# power.net
KiCad netlist of a schematic drawn in Altium Designer
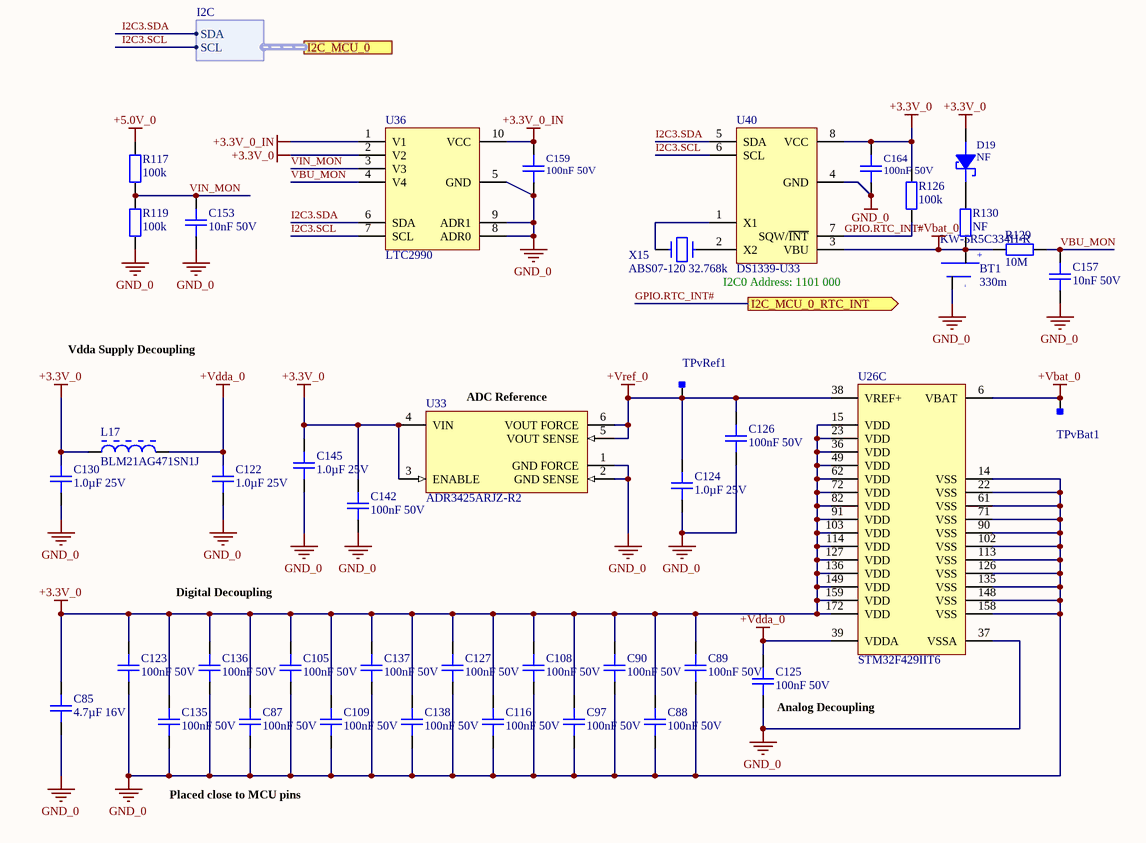
[diagram p0: power.SchDoc]

(export (version "E")
  (design (tool "Eeschema 10.0.6"))
  (components
    (comp (ref "BT1")
      (value "330m")
      (footprint "KW-5R5C")
      (description "Eaton 330mF, 5.5v, -20 to +80, Ultracapacitor, KW-5R5C334H-R")
      (fields (field (name "SUPPLIER PART NUMBER 1") "KW-5R5C334H-R"))
      (libsource (lib "master-010106") (part "BATTERY_1"))
    )
    (comp (ref "C85")
      (value "4.7µF 16V")
      (footprint "0805C")
      (description "Ceramic, 4.7µF, ±10%, 16V, X7R, –55 to 125°C, 0805 (2012),RoHS, Automotive")
      (fields (field (name "PART NUMBER") "GCJ21BR71C475KA01") (field (name "TOLERANCE") "±10%"))
      (libsource (lib "master-010106") (part "gen_C_ceramic_4u7_16V_X7R_0805"))
    )
    (comp (ref "C87")
      (value "100nF 50V")
      (footprint "0402C")
      (description "Ceramic, 100nF, ±10%, 50V, X7R, –55 to 125°C, 0402 (1005),RoHS, Automotive")
      (fields (field (name "PART NUMBER") "GCM155R71H104KE02") (field (name "TOLERANCE") "±10%"))
      (libsource (lib "master-010106") (part "gen_C_ceramic_100n_50V_X7R_0402"))
    )
    (comp (ref "C88")
      (value "100nF 50V")
      (footprint "0402C")
      (description "Ceramic, 100nF, ±10%, 50V, X7R, –55 to 125°C, 0402 (1005),RoHS, Automotive")
      (fields (field (name "PART NUMBER") "GCM155R71H104KE02") (field (name "TOLERANCE") "±10%"))
      (libsource (lib "master-010106") (part "gen_C_ceramic_100n_50V_X7R_0402"))
    )
    (comp (ref "C89")
      (value "100nF 50V")
      (footprint "0402C")
      (description "Ceramic, 100nF, ±10%, 50V, X7R, –55 to 125°C, 0402 (1005),RoHS, Automotive")
      (fields (field (name "PART NUMBER") "GCM155R71H104KE02") (field (name "TOLERANCE") "±10%"))
      (libsource (lib "master-010106") (part "gen_C_ceramic_100n_50V_X7R_0402"))
    )
    (comp (ref "C90")
      (value "100nF 50V")
      (footprint "0402C")
      (description "Ceramic, 100nF, ±10%, 50V, X7R, –55 to 125°C, 0402 (1005),RoHS, Automotive")
      (fields (field (name "PART NUMBER") "GCM155R71H104KE02") (field (name "TOLERANCE") "±10%"))
      (libsource (lib "master-010106") (part "gen_C_ceramic_100n_50V_X7R_0402"))
    )
    (comp (ref "C97")
      (value "100nF 50V")
      (footprint "0402C")
      (description "Ceramic, 100nF, ±10%, 50V, X7R, –55 to 125°C, 0402 (1005),RoHS, Automotive")
      (fields (field (name "PART NUMBER") "GCM155R71H104KE02") (field (name "TOLERANCE") "±10%"))
      (libsource (lib "master-010106") (part "gen_C_ceramic_100n_50V_X7R_0402"))
    )
    (comp (ref "C105")
      (value "100nF 50V")
      (footprint "0402C")
      (description "Ceramic, 100nF, ±10%, 50V, X7R, –55 to 125°C, 0402 (1005),RoHS, Automotive")
      (fields (field (name "PART NUMBER") "GCM155R71H104KE02") (field (name "TOLERANCE") "±10%"))
      (libsource (lib "master-010106") (part "gen_C_ceramic_100n_50V_X7R_0402"))
    )
    (comp (ref "C108")
      (value "100nF 50V")
      (footprint "0402C")
      (description "Ceramic, 100nF, ±10%, 50V, X7R, –55 to 125°C, 0402 (1005),RoHS, Automotive")
      (fields (field (name "PART NUMBER") "GCM155R71H104KE02") (field (name "TOLERANCE") "±10%"))
      (libsource (lib "master-010106") (part "gen_C_ceramic_100n_50V_X7R_0402"))
    )
    (comp (ref "C109")
      (value "100nF 50V")
      (footprint "0402C")
      (description "Ceramic, 100nF, ±10%, 50V, X7R, –55 to 125°C, 0402 (1005),RoHS, Automotive")
      (fields (field (name "PART NUMBER") "GCM155R71H104KE02") (field (name "TOLERANCE") "±10%"))
      (libsource (lib "master-010106") (part "gen_C_ceramic_100n_50V_X7R_0402"))
    )
    (comp (ref "C116")
      (value "100nF 50V")
      (footprint "0402C")
      (description "Ceramic, 100nF, ±10%, 50V, X7R, –55 to 125°C, 0402 (1005),RoHS, Automotive")
      (fields (field (name "PART NUMBER") "GCM155R71H104KE02") (field (name "TOLERANCE") "±10%"))
      (libsource (lib "master-010106") (part "gen_C_ceramic_100n_50V_X7R_0402"))
    )
    (comp (ref "C122")
      (value "1.0µF 25V")
      (footprint "0603C")
      (description "Ceramic, 1.0µF, ±10%, 25V, X7R, –55 to 125°C, 0603 (1608),RoHS, Automotive")
      (fields (field (name "PART NUMBER") "GCJ188R71E105KA01") (field (name "TOLERANCE") "±10%"))
      (libsource (lib "master-010106") (part "gen_C_ceramic_1u_25V_X7R_0603"))
    )
    (comp (ref "C123")
      (value "100nF 50V")
      (footprint "0402C")
      (description "Ceramic, 100nF, ±10%, 50V, X7R, –55 to 125°C, 0402 (1005),RoHS, Automotive")
      (fields (field (name "PART NUMBER") "GCM155R71H104KE02") (field (name "TOLERANCE") "±10%"))
      (libsource (lib "master-010106") (part "gen_C_ceramic_100n_50V_X7R_0402"))
    )
    (comp (ref "C124")
      (value "1.0µF 25V")
      (footprint "0603C")
      (description "Ceramic, 1.0µF, ±10%, 25V, X7R, –55 to 125°C, 0603 (1608),RoHS, Automotive")
      (fields (field (name "PART NUMBER") "GCJ188R71E105KA01") (field (name "TOLERANCE") "±10%"))
      (libsource (lib "master-010106") (part "gen_C_ceramic_1u_25V_X7R_0603"))
    )
    (comp (ref "C125")
      (value "100nF 50V")
      (footprint "0402C")
      (description "Ceramic, 100nF, ±10%, 50V, X7R, –55 to 125°C, 0402 (1005),RoHS, Automotive")
      (fields (field (name "PART NUMBER") "GCM155R71H104KE02") (field (name "TOLERANCE") "±10%"))
      (libsource (lib "master-010106") (part "gen_C_ceramic_100n_50V_X7R_0402"))
    )
    (comp (ref "C126")
      (value "100nF 50V")
      (footprint "0402C")
      (description "Ceramic, 100nF, ±10%, 50V, X7R, –55 to 125°C, 0402 (1005),RoHS, Automotive")
      (fields (field (name "PART NUMBER") "GCM155R71H104KE02") (field (name "TOLERANCE") "±10%"))
      (libsource (lib "master-010106") (part "gen_C_ceramic_100n_50V_X7R_0402"))
    )
    (comp (ref "C127")
      (value "100nF 50V")
      (footprint "0402C")
      (description "Ceramic, 100nF, ±10%, 50V, X7R, –55 to 125°C, 0402 (1005),RoHS, Automotive")
      (fields (field (name "PART NUMBER") "GCM155R71H104KE02") (field (name "TOLERANCE") "±10%"))
      (libsource (lib "master-010106") (part "gen_C_ceramic_100n_50V_X7R_0402"))
    )
    (comp (ref "C130")
      (value "1.0µF 25V")
      (footprint "0603C")
      (description "Ceramic, 1.0µF, ±10%, 25V, X7R, –55 to 125°C, 0603 (1608),RoHS, Automotive")
      (fields (field (name "PART NUMBER") "GCJ188R71E105KA01") (field (name "TOLERANCE") "±10%"))
      (libsource (lib "master-010106") (part "gen_C_ceramic_1u_25V_X7R_0603"))
    )
    (comp (ref "C135")
      (value "100nF 50V")
      (footprint "0402C")
      (description "Ceramic, 100nF, ±10%, 50V, X7R, –55 to 125°C, 0402 (1005),RoHS, Automotive")
      (fields (field (name "PART NUMBER") "GCM155R71H104KE02") (field (name "TOLERANCE") "±10%"))
      (libsource (lib "master-010106") (part "gen_C_ceramic_100n_50V_X7R_0402"))
    )
    (comp (ref "C136")
      (value "100nF 50V")
      (footprint "0402C")
      (description "Ceramic, 100nF, ±10%, 50V, X7R, –55 to 125°C, 0402 (1005),RoHS, Automotive")
      (fields (field (name "PART NUMBER") "GCM155R71H104KE02") (field (name "TOLERANCE") "±10%"))
      (libsource (lib "master-010106") (part "gen_C_ceramic_100n_50V_X7R_0402"))
    )
    (comp (ref "C137")
      (value "100nF 50V")
      (footprint "0402C")
      (description "Ceramic, 100nF, ±10%, 50V, X7R, –55 to 125°C, 0402 (1005),RoHS, Automotive")
      (fields (field (name "PART NUMBER") "GCM155R71H104KE02") (field (name "TOLERANCE") "±10%"))
      (libsource (lib "master-010106") (part "gen_C_ceramic_100n_50V_X7R_0402"))
    )
    (comp (ref "C138")
      (value "100nF 50V")
      (footprint "0402C")
      (description "Ceramic, 100nF, ±10%, 50V, X7R, –55 to 125°C, 0402 (1005),RoHS, Automotive")
      (fields (field (name "PART NUMBER") "GCM155R71H104KE02") (field (name "TOLERANCE") "±10%"))
      (libsource (lib "master-010106") (part "gen_C_ceramic_100n_50V_X7R_0402"))
    )
    (comp (ref "C142")
      (value "100nF 50V")
      (footprint "0603C")
      (description "Ceramic, 100nF, ±10%, 50V, X7R, –55 to 125°C, 0603 (1608),RoHS, Automotive")
      (fields (field (name "PART NUMBER") "GCJ188R71H104KA12") (field (name "TOLERANCE") "±10%"))
      (libsource (lib "master-010106") (part "C"))
    )
    (comp (ref "C145")
      (value "1.0µF 25V")
      (footprint "0603C")
      (description "Ceramic, 1.0µF, ±10%, 25V, X7R, –55 to 125°C, 0603 (1608),RoHS, Automotive")
      (fields (field (name "PART NUMBER") "GCJ188R71E105KA01") (field (name "TOLERANCE") "±10%"))
      (libsource (lib "master-010106") (part "gen_C_ceramic_1u_25V_X7R_0603"))
    )
    (comp (ref "C153")
      (value "10nF 50V")
      (footprint "0603C")
      (description "Ceramic, 10nF, ±10%, 50V, X7R, –55 to 125°C, 0603 (1608),RoHS, Automotive")
      (fields (field (name "PART NUMBER") "GCJ188R71H102KA01") (field (name "TOLERANCE") "±10%"))
      (libsource (lib "master-010106") (part "gen_C_ceramic_10n_50V_X7R_0603"))
    )
    (comp (ref "C157")
      (value "10nF 50V")
      (footprint "0603C")
      (description "Ceramic, 10nF, ±10%, 50V, X7R, –55 to 125°C, 0603 (1608),RoHS, Automotive")
      (fields (field (name "PART NUMBER") "GCJ188R71H102KA01") (field (name "TOLERANCE") "±10%"))
      (libsource (lib "master-010106") (part "gen_C_ceramic_10n_50V_X7R_0603"))
    )
    (comp (ref "C159")
      (value "100nF 50V")
      (footprint "0603C")
      (description "Ceramic, 100nF, ±10%, 50V, X7R, –55 to 125°C, 0603 (1608),RoHS, Automotive")
      (fields (field (name "PART NUMBER") "GCJ188R71H104KA12") (field (name "TOLERANCE") "±10%"))
      (libsource (lib "master-010106") (part "gen_C_ceramic_100n_50V_X7R_0603"))
    )
    (comp (ref "C164")
      (value "100nF 50V")
      (footprint "0603C")
      (description "Ceramic, 100nF, ±10%, 50V, X7R, –55 to 125°C, 0603 (1608),RoHS, Automotive")
      (fields (field (name "PART NUMBER") "GCJ188R71H104KA12") (field (name "TOLERANCE") "±10%"))
      (libsource (lib "master-010106") (part "gen_C_ceramic_100n_50V_X7R_0603"))
    )
    (comp (ref "D19")
      (value "NF")
      (description "BAT41 Schottky diode, small signal,SOD-523 package, RoHS compliant")
      (libsource (lib "*") (part "DIODE_SCHTKY"))
    )
    (comp (ref "L17")
      (value "BLM21AG471SN1J")
      (footprint "MURA-BLM21-H1-CHIP-2_V")
      (fields (field (name "MANUFACTURER") "Murata"))
      (libsource (lib "Altium Content Vault") (part "MURA-FB-2"))
    )
    (comp (ref "R117")
      (value "100k")
      (footprint "0603R")
      (description "SMD Resistor 100k 0603")
      (fields (field (name "PART NUMBER") "gen_R_100k_0603"))
      (libsource (lib "master-010106") (part "gen_R_100k_0603"))
    )
    (comp (ref "R119")
      (value "100k")
      (footprint "0603R")
      (description "SMD Resistor 100k 0603")
      (fields (field (name "PART NUMBER") "gen_R_100k_0603"))
      (libsource (lib "master-010106") (part "gen_R_100k_0603"))
    )
    (comp (ref "R126")
      (value "100k")
      (footprint "0603R")
      (description "SMD Resistor 100k 0603")
      (fields (field (name "PART NUMBER") "gen_R_100k_0603"))
      (libsource (lib "master-010106") (part "gen_R_100k_0603"))
    )
    (comp (ref "R129")
      (value "10M")
      (footprint "0603R")
      (description "SMD Resistor 10M 0603")
      (fields (field (name "PART NUMBER") "gen_R_10Meg_0603"))
      (libsource (lib "master-010106") (part "gen_R_10M_0603"))
    )
    (comp (ref "R130")
      (value "NF")
      (footprint "0603R")
      (description "SMD Resistor NF 0603")
      (fields (field (name "PART NUMBER") "gen_R_NF_0603"))
      (libsource (lib "master-010106") (part "gen_R_NF_0603"))
    )
    (comp (ref "TPvBat1")
      (value "Testpoint_Square")
      (footprint "Testpoint_S1")
      (description "Testpoint, square")
      (libsource (lib "OE750") (part "Testpoint_Square"))
    )
    (comp (ref "TPvRef1")
      (value "Testpoint_Square")
      (footprint "Testpoint_S1")
      (description "Testpoint, square")
      (libsource (lib "OE750") (part "Testpoint_Square"))
    )
    (comp (ref "U26")
      (value "STM32F429IIT6")
      (footprint "STM-LQFP176_N")
      (fields (field (name "MANUFACTURER") "STMicroelectronics"))
      (libsource (lib "ti-import") (part "MC-ARM-STM32F4X9-SQ176"))
    )
    (comp (ref "U33")
      (value "ADR3425ARJZ-R2")
      (footprint "ADI-RJ-6_N")
      (fields (field (name "MANUFACTURER") "Analog Devices"))
      (libsource (lib "Altium Content Vault") (part "ADI-ADR34xx-RJ-6"))
    )
    (comp (ref "U36") (value "LTC2990") (footprint "MSOP-10") (libsource (lib "25157") (part "LTC2990")))
    (comp (ref "U40") (value "DS1339-U33") (footprint "USOP-8") (libsource (lib "25157") (part "DS1339-U33")))
    (comp (ref "X15")
      (value "ABS07-120 32.768k")
      (footprint "ABS07")
      (libsource (lib "IntelliDesign") (part "CRYSTAL1"))
    )
  )
  (nets
    (net (code "2") (name "+3.3V_0") (class "Default")
      (node (ref "C105") (pin "1") (pinfunction "1_1") (pintype "passive"))
      (node (ref "C108") (pin "1") (pinfunction "1_1") (pintype "passive"))
      (node (ref "C109") (pin "1") (pinfunction "1_1") (pintype "passive"))
      (node (ref "C116") (pin "1") (pinfunction "1_1") (pintype "passive"))
      (node (ref "C123") (pin "1") (pinfunction "1_1") (pintype "passive"))
      (node (ref "C127") (pin "1") (pinfunction "1_1") (pintype "passive"))
      (node (ref "C130") (pin "1") (pinfunction "1_1") (pintype "passive"))
      (node (ref "C135") (pin "1") (pinfunction "1_1") (pintype "passive"))
      (node (ref "C136") (pin "1") (pinfunction "1_1") (pintype "passive"))
      (node (ref "C137") (pin "1") (pinfunction "1_1") (pintype "passive"))
      (node (ref "C138") (pin "1") (pinfunction "1_1") (pintype "passive"))
      (node (ref "C142") (pin "1") (pinfunction "1_1") (pintype "passive"))
      (node (ref "C145") (pin "1") (pinfunction "1_1") (pintype "passive"))
      (node (ref "C164") (pin "1") (pinfunction "1_1") (pintype "passive"))
      (node (ref "C85") (pin "1") (pinfunction "1_1") (pintype "passive"))
      (node (ref "C87") (pin "1") (pinfunction "1_1") (pintype "passive"))
      (node (ref "C88") (pin "1") (pinfunction "1_1") (pintype "passive"))
      (node (ref "C89") (pin "1") (pinfunction "1_1") (pintype "passive"))
      (node (ref "C90") (pin "1") (pinfunction "1_1") (pintype "passive"))
      (node (ref "C97") (pin "1") (pinfunction "1_1") (pintype "passive"))
      (node (ref "D19") (pin "1") (pinfunction "A_1") (pintype "passive"))
      (node (ref "L17") (pin "1") (pinfunction "1_1") (pintype "passive"))
      (node (ref "R126") (pin "2") (pinfunction "2_2") (pintype "passive"))
      (node (ref "U26") (pin "103") (pinfunction "VDD_103") (pintype "power_in"))
      (node (ref "U26") (pin "114") (pinfunction "VDD_114") (pintype "power_in"))
      (node (ref "U26") (pin "127") (pinfunction "VDD_127") (pintype "power_in"))
      (node (ref "U26") (pin "136") (pinfunction "VDD_136") (pintype "power_in"))
      (node (ref "U26") (pin "149") (pinfunction "VDD_149") (pintype "power_in"))
      (node (ref "U26") (pin "15") (pinfunction "VDD_15") (pintype "power_in"))
      (node (ref "U26") (pin "159") (pinfunction "VDD_159") (pintype "power_in"))
      (node (ref "U26") (pin "172") (pinfunction "VDD_172") (pintype "power_in"))
      (node (ref "U26") (pin "23") (pinfunction "VDD_23") (pintype "power_in"))
      (node (ref "U26") (pin "36") (pinfunction "VDD_36") (pintype "power_in"))
      (node (ref "U26") (pin "49") (pinfunction "VDD_49") (pintype "power_in"))
      (node (ref "U26") (pin "62") (pinfunction "VDD_62") (pintype "power_in"))
      (node (ref "U26") (pin "72") (pinfunction "VDD_72") (pintype "power_in"))
      (node (ref "U26") (pin "82") (pinfunction "VDD_82") (pintype "power_in"))
      (node (ref "U26") (pin "91") (pinfunction "VDD_91") (pintype "power_in"))
      (node (ref "U33") (pin "3") (pinfunction "ENABLE_3") (pintype "input"))
      (node (ref "U33") (pin "4") (pinfunction "VIN_4") (pintype "power_in"))
      (node (ref "U36") (pin "2") (pinfunction "V2_2") (pintype "passive"))
      (node (ref "U40") (pin "8") (pinfunction "VCC_8") (pintype "passive"))
    )
    (net (code "3") (name "+3.3V_0_IN") (class "Default")
      (node (ref "C159") (pin "1") (pinfunction "1_1") (pintype "passive"))
      (node (ref "U36") (pin "1") (pinfunction "V1_1") (pintype "passive"))
      (node (ref "U36") (pin "10") (pinfunction "VCC_10") (pintype "passive"))
    )
    (net (code "4") (name "+5.0V_0") (class "Default")
      (node (ref "R117") (pin "2") (pinfunction "2_2") (pintype "passive"))
    )
    (net (code "5") (name "+Vbat_0") (class "Default")
      (node (ref "BT1") (pin "1") (pinfunction "pos1_1") (pintype "passive"))
      (node (ref "R129") (pin "2") (pinfunction "2_2") (pintype "passive"))
      (node (ref "R130") (pin "2") (pinfunction "2_2") (pintype "passive"))
      (node (ref "TPvBat1") (pin "1") (pinfunction "1_1") (pintype "passive"))
      (node (ref "U26") (pin "6") (pinfunction "VBAT_6") (pintype "power_in"))
      (node (ref "U40") (pin "3") (pinfunction "VBU_3") (pintype "passive"))
    )
    (net (code "6") (name "+Vdda_0") (class "Default")
      (node (ref "C122") (pin "1") (pinfunction "1_1") (pintype "passive"))
      (node (ref "C125") (pin "1") (pinfunction "1_1") (pintype "passive"))
      (node (ref "L17") (pin "2") (pinfunction "2_2") (pintype "passive"))
      (node (ref "U26") (pin "39") (pinfunction "VDDA_39") (pintype "power_in"))
    )
    (net (code "7") (name "+Vref_0") (class "Default")
      (node (ref "C124") (pin "1") (pinfunction "1_1") (pintype "passive"))
      (node (ref "C126") (pin "1") (pinfunction "1_1") (pintype "passive"))
      (node (ref "TPvRef1") (pin "1") (pinfunction "1_1") (pintype "passive"))
      (node (ref "U26") (pin "38") (pinfunction "VREF+_38") (pintype "power_in"))
      (node (ref "U33") (pin "5") (pinfunction "VOUT_SENSE_5") (pintype "input"))
      (node (ref "U33") (pin "6") (pinfunction "VOUT_FORCE_6") (pintype "power_in"))
    )
    (net (code "8") (name "/GPIO.RTC_INT#") (class "Default")
      (node (ref "R126") (pin "1") (pinfunction "1_1") (pintype "passive"))
      (node (ref "U40") (pin "7") (pinfunction "SQW/~{INT}_7") (pintype "passive"))
    )
    (net (code "9") (name "/I2C3.SCL") (class "Default")
      (node (ref "U36") (pin "7") (pinfunction "SCL_7") (pintype "passive"))
      (node (ref "U40") (pin "6") (pinfunction "SCL_6") (pintype "passive"))
    )
    (net (code "10") (name "/I2C3.SDA") (class "Default")
      (node (ref "U36") (pin "6") (pinfunction "SDA_6") (pintype "passive"))
      (node (ref "U40") (pin "5") (pinfunction "SDA_5") (pintype "passive"))
    )
    (net (code "11") (name "/VBU_MON") (class "Default")
      (node (ref "C157") (pin "2") (pinfunction "2_2") (pintype "passive"))
      (node (ref "R129") (pin "1") (pinfunction "1_1") (pintype "passive"))
      (node (ref "U36") (pin "4") (pinfunction "V4_4") (pintype "passive"))
    )
    (net (code "12") (name "/VIN_MON") (class "Default")
      (node (ref "C153") (pin "2") (pinfunction "2_2") (pintype "passive"))
      (node (ref "R117") (pin "1") (pinfunction "1_1") (pintype "passive"))
      (node (ref "R119") (pin "2") (pinfunction "2_2") (pintype "passive"))
      (node (ref "U36") (pin "3") (pinfunction "V3_3") (pintype "passive"))
    )
    (net (code "14") (name "GND_0") (class "Default")
      (node (ref "BT1") (pin "2") (pinfunction "neg_2") (pintype "passive"))
      (node (ref "C105") (pin "2") (pinfunction "2_2") (pintype "passive"))
      (node (ref "C108") (pin "2") (pinfunction "2_2") (pintype "passive"))
      (node (ref "C109") (pin "2") (pinfunction "2_2") (pintype "passive"))
      (node (ref "C116") (pin "2") (pinfunction "2_2") (pintype "passive"))
      (node (ref "C122") (pin "2") (pinfunction "2_2") (pintype "passive"))
      (node (ref "C123") (pin "2") (pinfunction "2_2") (pintype "passive"))
      (node (ref "C124") (pin "2") (pinfunction "2_2") (pintype "passive"))
      (node (ref "C125") (pin "2") (pinfunction "2_2") (pintype "passive"))
      (node (ref "C126") (pin "2") (pinfunction "2_2") (pintype "passive"))
      (node (ref "C127") (pin "2") (pinfunction "2_2") (pintype "passive"))
      (node (ref "C130") (pin "2") (pinfunction "2_2") (pintype "passive"))
      (node (ref "C135") (pin "2") (pinfunction "2_2") (pintype "passive"))
      (node (ref "C136") (pin "2") (pinfunction "2_2") (pintype "passive"))
      (node (ref "C137") (pin "2") (pinfunction "2_2") (pintype "passive"))
      (node (ref "C138") (pin "2") (pinfunction "2_2") (pintype "passive"))
      (node (ref "C142") (pin "2") (pinfunction "2_2") (pintype "passive"))
      (node (ref "C145") (pin "2") (pinfunction "2_2") (pintype "passive"))
      (node (ref "C153") (pin "1") (pinfunction "1_1") (pintype "passive"))
      (node (ref "C157") (pin "1") (pinfunction "1_1") (pintype "passive"))
      (node (ref "C159") (pin "2") (pinfunction "2_2") (pintype "passive"))
      (node (ref "C164") (pin "2") (pinfunction "2_2") (pintype "passive"))
      (node (ref "C85") (pin "2") (pinfunction "2_2") (pintype "passive"))
      (node (ref "C87") (pin "2") (pinfunction "2_2") (pintype "passive"))
      (node (ref "C88") (pin "2") (pinfunction "2_2") (pintype "passive"))
      (node (ref "C89") (pin "2") (pinfunction "2_2") (pintype "passive"))
      (node (ref "C90") (pin "2") (pinfunction "2_2") (pintype "passive"))
      (node (ref "C97") (pin "2") (pinfunction "2_2") (pintype "passive"))
      (node (ref "R119") (pin "1") (pinfunction "1_1") (pintype "passive"))
      (node (ref "U26") (pin "102") (pinfunction "VSS_102") (pintype "power_in"))
      (node (ref "U26") (pin "113") (pinfunction "VSS_113") (pintype "power_in"))
      (node (ref "U26") (pin "126") (pinfunction "VSS_126") (pintype "power_in"))
      (node (ref "U26") (pin "135") (pinfunction "VSS_135") (pintype "power_in"))
      (node (ref "U26") (pin "14") (pinfunction "VSS_14") (pintype "power_in"))
      (node (ref "U26") (pin "148") (pinfunction "VSS_148") (pintype "power_in"))
      (node (ref "U26") (pin "158") (pinfunction "VSS_158") (pintype "power_in"))
      (node (ref "U26") (pin "22") (pinfunction "VSS_22") (pintype "power_in"))
      (node (ref "U26") (pin "37") (pinfunction "VSSA_37") (pintype "power_in"))
      (node (ref "U26") (pin "61") (pinfunction "VSS_61") (pintype "power_in"))
      (node (ref "U26") (pin "71") (pinfunction "VSS_71") (pintype "power_in"))
      (node (ref "U26") (pin "90") (pinfunction "VSS_90") (pintype "power_in"))
      (node (ref "U33") (pin "1") (pinfunction "GND_FORCE_1") (pintype "power_in"))
      (node (ref "U33") (pin "2") (pinfunction "GND_SENSE_2") (pintype "input"))
      (node (ref "U36") (pin "5") (pinfunction "GND_5") (pintype "passive"))
      (node (ref "U36") (pin "8") (pinfunction "ADR0_8") (pintype "passive"))
      (node (ref "U36") (pin "9") (pinfunction "ADR1_9") (pintype "passive"))
      (node (ref "U40") (pin "4") (pinfunction "GND_4") (pintype "passive"))
    )
    (net (code "15") (name "Net-(D19-C)") (class "Default")
      (node (ref "D19") (pin "2") (pinfunction "C_2") (pintype "passive"))
      (node (ref "R130") (pin "1") (pinfunction "1_1") (pintype "passive"))
    )
    (net (code "16") (name "Net-(U40-X1)") (class "Default")
      (node (ref "U40") (pin "1") (pinfunction "X1_1") (pintype "passive"))
      (node (ref "X15") (pin "2") (pintype "passive"))
    )
    (net (code "17") (name "Net-(U40-X2)") (class "Default")
      (node (ref "U40") (pin "2") (pinfunction "X2_2") (pintype "passive"))
      (node (ref "X15") (pin "1") (pintype "passive"))
    )
  )
)
